# project_buran_schematic.net
KiCad netlist of a schematic drawn in Altium Designer
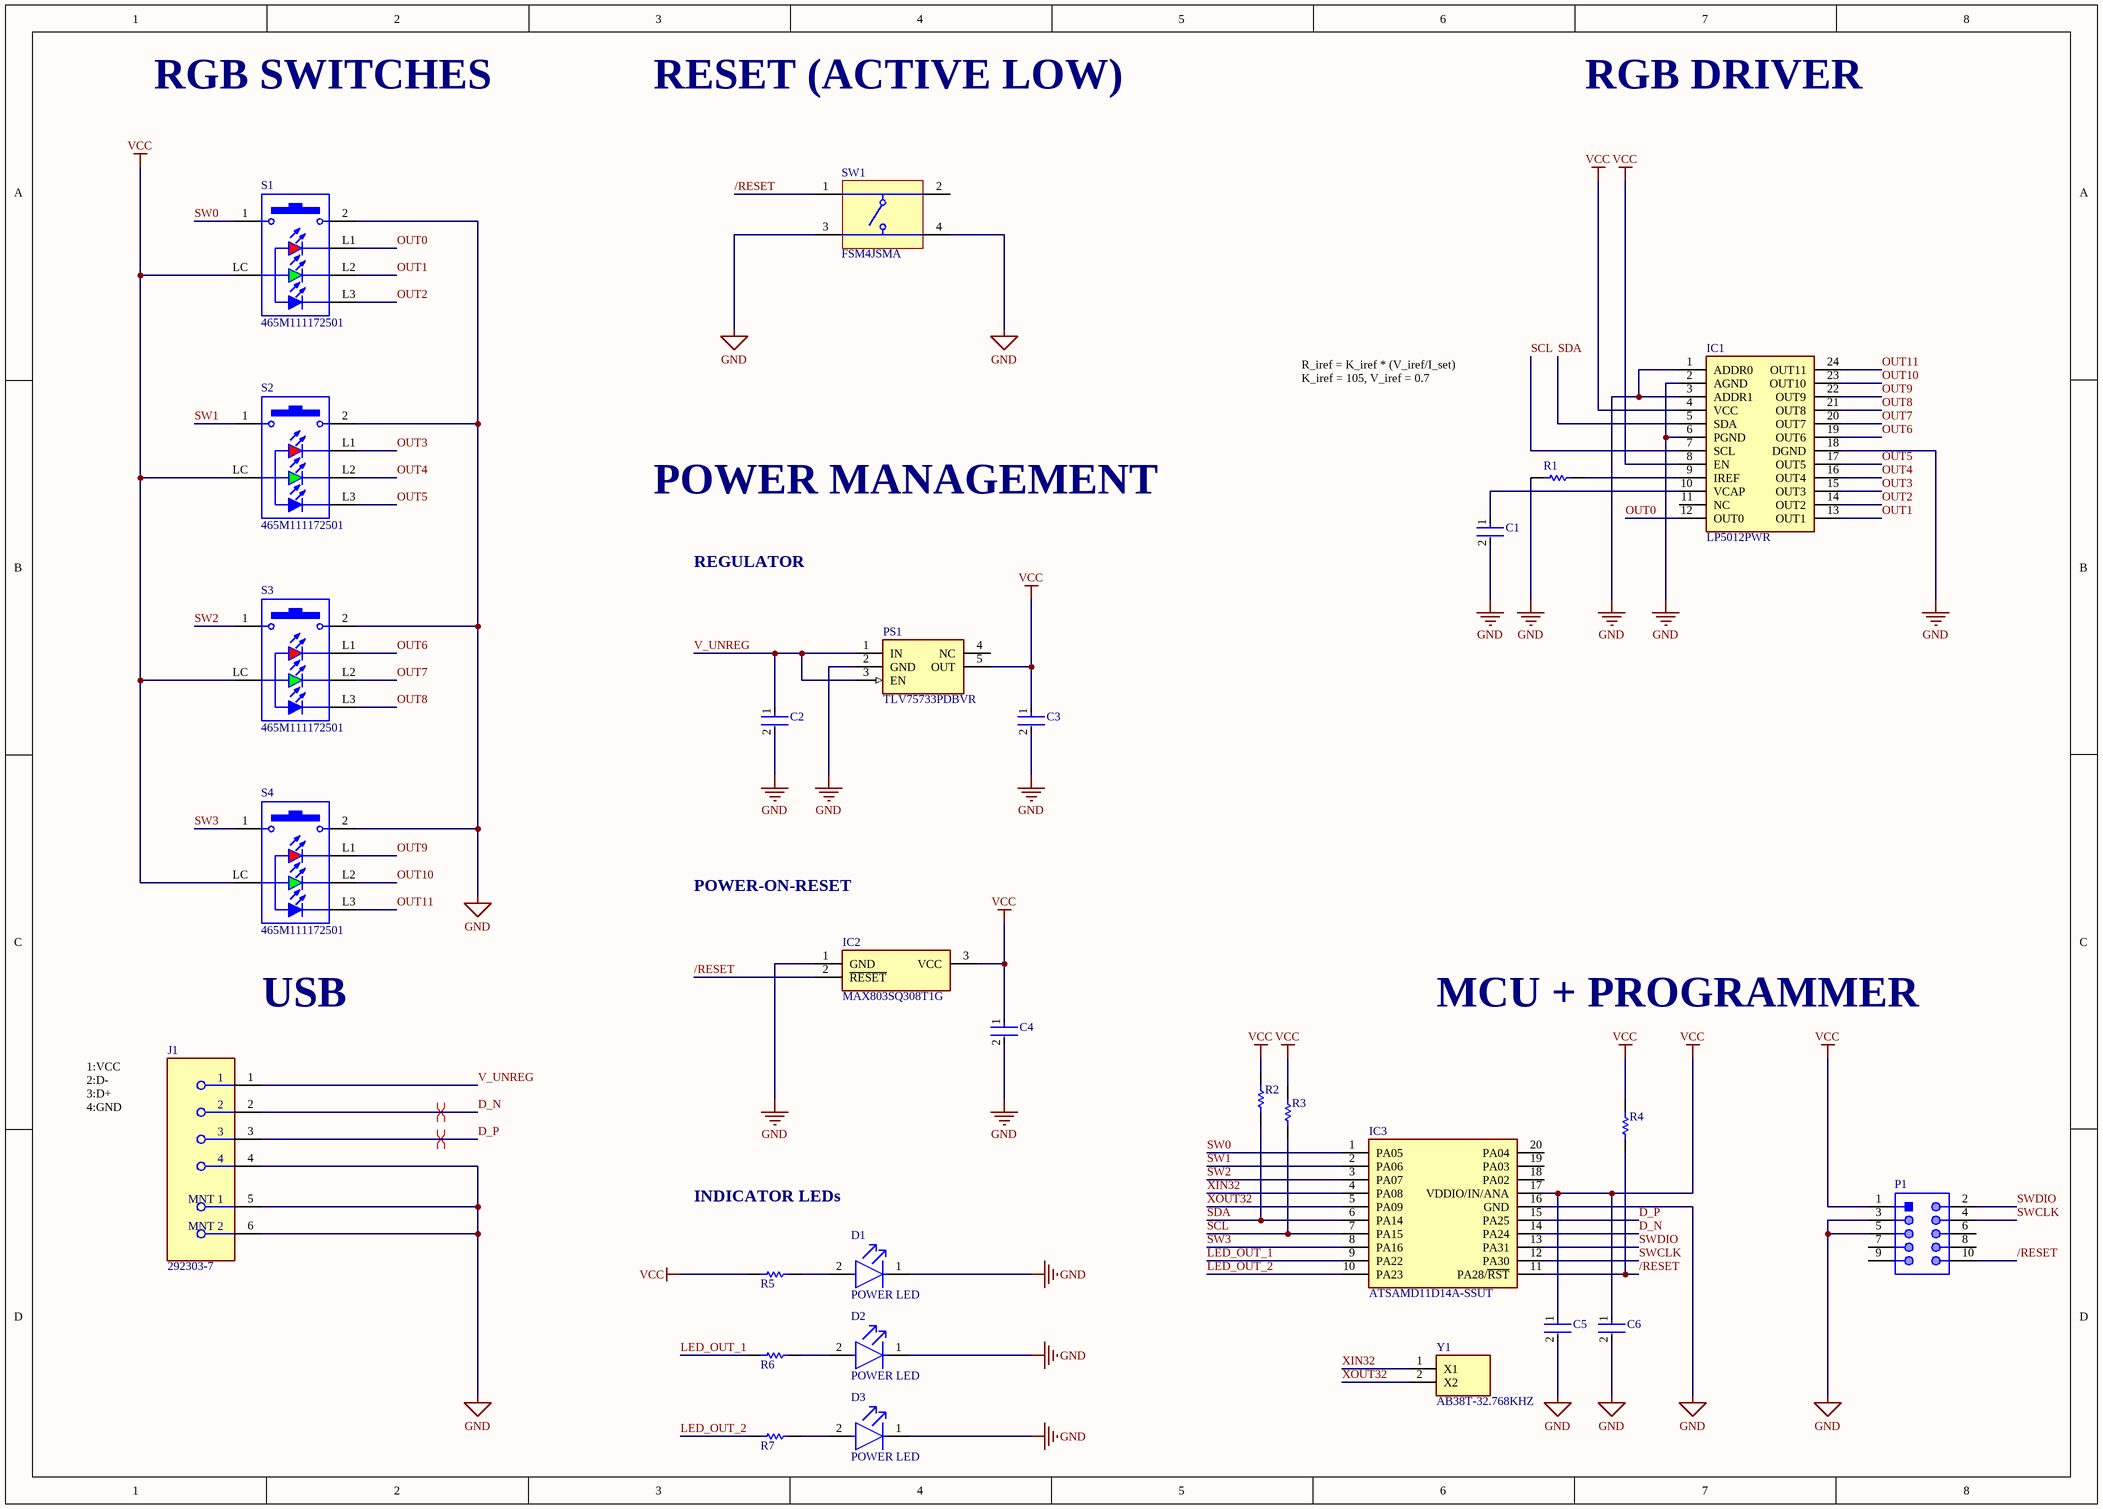
[diagram p0: project_buran_schematic.SchDoc]

(export (version "E")
  (design (tool "Eeschema 10.0.6"))
  (components
    (comp (ref "C1")
      (value "GRM188R60J106ME47D")
      (footprint "FP-GRM188-0_1-e0_2_0_55-IPC_A")
      (description "Chip Multilayer Ceramic Capacitors for General Purpose, 0603, 10uF, X5R, 15%, 20%, 6.3V")
      (fields (field (name "VOLTAGE") "6.3V") (field (name "TOLERANCE") "20%"))
      (libsource (lib "Altium Content Vault") (part "02cd4be3c70576c341d710602a673aa"))
    )
    (comp (ref "C2")
      (value "GRM188R60J106ME47D")
      (footprint "FP-GRM188-0_1-e0_2_0_55-IPC_A")
      (description "Chip Multilayer Ceramic Capacitors for General Purpose, 0603, 10uF, X5R, 15%, 20%, 6.3V")
      (fields (field (name "VOLTAGE") "6.3V") (field (name "TOLERANCE") "20%"))
      (libsource (lib "Altium Content Vault") (part "02cd4be3c70576c341d710602a673aa"))
    )
    (comp (ref "C3")
      (value "GRM188R60J106ME47D")
      (footprint "FP-GRM188-0_1-e0_2_0_55-IPC_A")
      (description "Chip Multilayer Ceramic Capacitors for General Purpose, 0603, 10uF, X5R, 15%, 20%, 6.3V")
      (fields (field (name "VOLTAGE") "6.3V") (field (name "TOLERANCE") "20%"))
      (libsource (lib "Altium Content Vault") (part "02cd4be3c70576c341d710602a673aa"))
    )
    (comp (ref "C4")
      (value "GRM188R60J106ME47D")
      (footprint "FP-GRM188-0_1-e0_2_0_55-IPC_A")
      (description "Chip Multilayer Ceramic Capacitors for General Purpose, 0603, 10uF, X5R, 15%, 20%, 6.3V")
      (fields (field (name "VOLTAGE") "6.3V") (field (name "TOLERANCE") "20%"))
      (libsource (lib "Altium Content Vault") (part "02cd4be3c70576c341d710602a673aa"))
    )
    (comp (ref "C5")
      (value "GRM188R60J106ME47D")
      (footprint "FP-GRM188-0_1-e0_2_0_55-IPC_A")
      (description "Chip Multilayer Ceramic Capacitors for General Purpose, 0603, 10uF, X5R, 15%, 20%, 6.3V")
      (fields (field (name "VOLTAGE") "6.3V") (field (name "TOLERANCE") "20%"))
      (libsource (lib "Altium Content Vault") (part "02cd4be3c70576c341d710602a673aa"))
    )
    (comp (ref "C6")
      (value "GRM188R60J106ME47D")
      (footprint "FP-GRM188-0_1-e0_2_0_55-IPC_A")
      (description "Chip Multilayer Ceramic Capacitors for General Purpose, 0603, 10uF, X5R, 15%, 20%, 6.3V")
      (fields (field (name "VOLTAGE") "6.3V") (field (name "TOLERANCE") "20%"))
      (libsource (lib "Altium Content Vault") (part "02cd4be3c70576c341d710602a673aa"))
    )
    (comp (ref "D1")
      (value "POWER LED")
      (footprint "FP-LTST-C190GKT-MFG")
      (description "LED GREEN CLEAR CHIP SMD")
      (fields (field (name "VOLTAGE") "2V"))
      (libsource (lib "Altium Content Vault") (part "8706943c75ba83719d021d2fdc84c58"))
    )
    (comp (ref "D2")
      (value "POWER LED")
      (footprint "FP-LTST-C190GKT-MFG")
      (description "LED GREEN CLEAR CHIP SMD")
      (fields (field (name "VOLTAGE") "2V"))
      (libsource (lib "Altium Content Vault") (part "8706943c75ba83719d021d2fdc84c58"))
    )
    (comp (ref "D3")
      (value "POWER LED")
      (footprint "FP-LTST-C190GKT-MFG")
      (description "LED GREEN CLEAR CHIP SMD")
      (fields (field (name "VOLTAGE") "2V"))
      (libsource (lib "Altium Content Vault") (part "8706943c75ba83719d021d2fdc84c58"))
    )
    (comp (ref "IC1")
      (value "LP5012PWR")
      (footprint "SOP65P640X120-24N")
      (description "Integrated Circuit")
      (fields (field (name "MOUSER PART NUMBER") "595-LP5012PWR"))
      (libsource (lib "*") (part "LP5012PWR"))
    )
    (comp (ref "IC2")
      (value "MAX803SQ308T1G")
      (footprint "SamacSys:SOT65P220X100-3N")
      (description "Integrated Circuit")
      (fields (field (name "MOUSER PART NUMBER") "863-MAX803SQ308T1G"))
      (libsource (lib "*") (part "MAX803SQ308T1G"))
    )
    (comp (ref "IC3")
      (value "ATSAMD11D14A-SSUT")
      (footprint "SamacSys:SOIC127P1032X265-20N")
      (description "Integrated Circuit")
      (fields (field (name "MOUSER PART NUMBER") "556-ATSAMD11D14ASSUT"))
      (libsource (lib "*") (part "ATSAMD11D14A-SSUT"))
    )
    (comp (ref "J1")
      (value "292303-7")
      (footprint "FP-292303-7-MFG")
      (description "CONN RCPT USB2.0 TYPEA 4P SMD RA")
      (fields
        (field (name "OCTOPART") "https://octopart.com/292303-7-te+connectivity-42840369")
        (field (name "MANUFACTURER") "TE Connectivity")
      )
      (libsource (lib "Altium Content Vault") (part "79e6714efa0bb2f851c24b2688127c9"))
    )
    (comp (ref "P1")
      (value "61301021121")
      (footprint "61301021121")
      (description "THT Vertical Pin Header WR-PHD, Pitch 2.54 mm, Dual Row, 10 pins")
      (fields (field (name "MANUFACTURER") "Wurth Elektronik") (field (name "PUBLISHER") "WurthElektronik"))
      (libsource (lib "Altium Content Vault") (part "WE-CN-2P-M-R10"))
    )
    (comp (ref "PS1")
      (value "TLV75733PDBVR")
      (footprint "SamacSys:SOT95P280X145-5N")
      (description "Power Supply")
      (fields (field (name "MOUSER PART NUMBER") "595-TLV75733PDBVR"))
      (libsource (lib "SamacSys") (part "TLV75733PDBVR"))
    )
    (comp (ref "R1")
      (value "CRCW0603110RFKEA")
      (footprint "RESC1609X50X30NL10T20")
      (fields (field (name "MANUFACTURER") "Vishay Dale"))
      (libsource (lib "Altium Content Vault") (part "RES"))
    )
    (comp (ref "R2")
      (value "CRCW0603110RFKEA")
      (footprint "RESC1609X50X30NL10T20")
      (fields (field (name "MANUFACTURER") "Vishay Dale"))
      (libsource (lib "Altium Content Vault") (part "RES"))
    )
    (comp (ref "R3")
      (value "CRCW0603110RFKEA")
      (footprint "RESC1609X50X30NL10T20")
      (fields (field (name "MANUFACTURER") "Vishay Dale"))
      (libsource (lib "Altium Content Vault") (part "RES"))
    )
    (comp (ref "R4")
      (value "CRCW0603110RFKEA")
      (footprint "RESC1609X50X30NL10T20")
      (fields (field (name "MANUFACTURER") "Vishay Dale"))
      (libsource (lib "Altium Content Vault") (part "RES"))
    )
    (comp (ref "R5")
      (value "CRCW0603110RFKEA")
      (footprint "RESC1609X50X30NL10T20")
      (fields (field (name "MANUFACTURER") "Vishay Dale"))
      (libsource (lib "Altium Content Vault") (part "RES"))
    )
    (comp (ref "R6")
      (value "CRCW0603110RFKEA")
      (footprint "RESC1609X50X30NL10T20")
      (fields (field (name "MANUFACTURER") "Vishay Dale"))
      (libsource (lib "Altium Content Vault") (part "RES"))
    )
    (comp (ref "R7")
      (value "CRCW0603110RFKEA")
      (footprint "RESC1609X50X30NL10T20")
      (fields (field (name "MANUFACTURER") "Vishay Dale"))
      (libsource (lib "Altium Content Vault") (part "RES"))
    )
    (comp (ref "S1")
      (value "465M111172501")
      (footprint "465M111172501")
      (description "WS-PBTL Illuminated THT Push Button Switch, Red & Green & Blue")
      (fields (field (name "PUBLISHER") "Wurth Elektronik"))
      (libsource (lib "Altium_WS-PBTL (rev19a)") (part "465M111172501"))
    )
    (comp (ref "S2")
      (value "465M111172501")
      (footprint "465M111172501")
      (description "WS-PBTL Illuminated THT Push Button Switch, Red & Green & Blue")
      (fields (field (name "PUBLISHER") "Wurth Elektronik"))
      (libsource (lib "Altium_WS-PBTL (rev19a)") (part "465M111172501"))
    )
    (comp (ref "S3")
      (value "465M111172501")
      (footprint "465M111172501")
      (description "WS-PBTL Illuminated THT Push Button Switch, Red & Green & Blue")
      (fields (field (name "PUBLISHER") "Wurth Elektronik"))
      (libsource (lib "Altium_WS-PBTL (rev19a)") (part "465M111172501"))
    )
    (comp (ref "S4")
      (value "465M111172501")
      (footprint "465M111172501")
      (description "WS-PBTL Illuminated THT Push Button Switch, Red & Green & Blue")
      (fields (field (name "PUBLISHER") "Wurth Elektronik"))
      (libsource (lib "Altium_WS-PBTL (rev19a)") (part "465M111172501"))
    )
    (comp (ref "SW1")
      (value "FSM4JSMA")
      (footprint "TECO-FSM4JSMA_V")
      (description "Swicth, SPST, 24 V, -35 to 85 degC, 4-Pin SMD, RoHS, Tape and Reel")
      (fields (field (name "MANUFACTURER") "TE Connectivity"))
      (libsource (lib "Altium Content Vault") (part "SW-SPST-4_A"))
    )
    (comp (ref "Y1")
      (value "AB38T-32.768KHZ")
      (footprint "SamacSys:AB38T32768KHZ")
      (description "Crystal or Oscillator")
      (fields (field (name "MOUSER PART NUMBER") "815-AB38T-32.768KHZ"))
      (libsource (lib "SamacSys") (part "AB38T-32.768KHZ"))
    )
  )
  (nets
    (net (code "1") (name "/D_N") (class "Default")
      (node (ref "IC3") (pin "14") (pinfunction "PA24_14") (pintype "passive"))
      (node (ref "J1") (pin "2") (pinfunction "2_2") (pintype "passive"))
    )
    (net (code "2") (name "/D_P") (class "Default")
      (node (ref "IC3") (pin "15") (pinfunction "PA25_15") (pintype "passive"))
      (node (ref "J1") (pin "3") (pinfunction "3_3") (pintype "passive"))
    )
    (net (code "3") (name "/LED_OUT_1") (class "Default")
      (node (ref "IC3") (pin "9") (pinfunction "PA22_9") (pintype "passive"))
      (node (ref "R6") (pin "2") (pinfunction "2_2") (pintype "passive"))
    )
    (net (code "4") (name "/LED_OUT_2") (class "Default")
      (node (ref "IC3") (pin "10") (pinfunction "PA23_10") (pintype "passive"))
      (node (ref "R7") (pin "2") (pinfunction "2_2") (pintype "passive"))
    )
    (net (code "5") (name "/OUT0") (class "Default")
      (node (ref "IC1") (pin "12") (pinfunction "OUT0_12") (pintype "passive"))
      (node (ref "S1") (pin "L1") (pinfunction "L1_L1") (pintype "passive"))
    )
    (net (code "6") (name "/OUT1") (class "Default")
      (node (ref "IC1") (pin "13") (pinfunction "OUT1_13") (pintype "passive"))
      (node (ref "S1") (pin "L2") (pinfunction "L2_L2") (pintype "passive"))
    )
    (net (code "7") (name "/OUT2") (class "Default")
      (node (ref "IC1") (pin "14") (pinfunction "OUT2_14") (pintype "passive"))
      (node (ref "S1") (pin "L3") (pinfunction "L3_L3") (pintype "passive"))
    )
    (net (code "8") (name "/OUT3") (class "Default")
      (node (ref "IC1") (pin "15") (pinfunction "OUT3_15") (pintype "passive"))
      (node (ref "S2") (pin "L1") (pinfunction "L1_L1") (pintype "passive"))
    )
    (net (code "9") (name "/OUT4") (class "Default")
      (node (ref "IC1") (pin "16") (pinfunction "OUT4_16") (pintype "passive"))
      (node (ref "S2") (pin "L2") (pinfunction "L2_L2") (pintype "passive"))
    )
    (net (code "10") (name "/OUT5") (class "Default")
      (node (ref "IC1") (pin "17") (pinfunction "OUT5_17") (pintype "passive"))
      (node (ref "S2") (pin "L3") (pinfunction "L3_L3") (pintype "passive"))
    )
    (net (code "11") (name "/OUT6") (class "Default")
      (node (ref "IC1") (pin "19") (pinfunction "OUT6_19") (pintype "passive"))
      (node (ref "S3") (pin "L1") (pinfunction "L1_L1") (pintype "passive"))
    )
    (net (code "12") (name "/OUT7") (class "Default")
      (node (ref "IC1") (pin "20") (pinfunction "OUT7_20") (pintype "passive"))
      (node (ref "S3") (pin "L2") (pinfunction "L2_L2") (pintype "passive"))
    )
    (net (code "13") (name "/OUT8") (class "Default")
      (node (ref "IC1") (pin "21") (pinfunction "OUT8_21") (pintype "passive"))
      (node (ref "S3") (pin "L3") (pinfunction "L3_L3") (pintype "passive"))
    )
    (net (code "14") (name "/OUT9") (class "Default")
      (node (ref "IC1") (pin "22") (pinfunction "OUT9_22") (pintype "passive"))
      (node (ref "S4") (pin "L1") (pinfunction "L1_L1") (pintype "passive"))
    )
    (net (code "15") (name "/OUT10") (class "Default")
      (node (ref "IC1") (pin "23") (pinfunction "OUT10_23") (pintype "passive"))
      (node (ref "S4") (pin "L2") (pinfunction "L2_L2") (pintype "passive"))
    )
    (net (code "16") (name "/OUT11") (class "Default")
      (node (ref "IC1") (pin "24") (pinfunction "OUT11_24") (pintype "passive"))
      (node (ref "S4") (pin "L3") (pinfunction "L3_L3") (pintype "passive"))
    )
    (net (code "17") (name "/SCL") (class "Default")
      (node (ref "IC1") (pin "7") (pinfunction "SCL_7") (pintype "passive"))
      (node (ref "IC3") (pin "7") (pinfunction "PA15_7") (pintype "passive"))
      (node (ref "R3") (pin "1") (pinfunction "1_1") (pintype "passive"))
    )
    (net (code "18") (name "/SDA") (class "Default")
      (node (ref "IC1") (pin "5") (pinfunction "SDA_5") (pintype "passive"))
      (node (ref "IC3") (pin "6") (pinfunction "PA14_6") (pintype "passive"))
      (node (ref "R2") (pin "1") (pinfunction "1_1") (pintype "passive"))
    )
    (net (code "19") (name "/SW0") (class "Default")
      (node (ref "IC3") (pin "1") (pinfunction "PA05_1") (pintype "passive"))
      (node (ref "S1") (pin "1") (pinfunction "1_1") (pintype "passive"))
    )
    (net (code "20") (name "/SW1") (class "Default")
      (node (ref "IC3") (pin "2") (pinfunction "PA06_2") (pintype "passive"))
      (node (ref "S2") (pin "1") (pinfunction "1_1") (pintype "passive"))
    )
    (net (code "21") (name "/SW2") (class "Default")
      (node (ref "IC3") (pin "3") (pinfunction "PA07_3") (pintype "passive"))
      (node (ref "S3") (pin "1") (pinfunction "1_1") (pintype "passive"))
    )
    (net (code "22") (name "/SW3") (class "Default")
      (node (ref "IC3") (pin "8") (pinfunction "PA16_8") (pintype "passive"))
      (node (ref "S4") (pin "1") (pinfunction "1_1") (pintype "passive"))
    )
    (net (code "23") (name "/SWCLK") (class "Default")
      (node (ref "IC3") (pin "12") (pinfunction "PA30_12") (pintype "passive"))
      (node (ref "P1") (pin "4") (pinfunction "4_4") (pintype "passive"))
    )
    (net (code "24") (name "/SWDIO") (class "Default")
      (node (ref "IC3") (pin "13") (pinfunction "PA31_13") (pintype "passive"))
      (node (ref "P1") (pin "2") (pinfunction "2_2") (pintype "passive"))
    )
    (net (code "25") (name "/V_UNREG") (class "Default")
      (node (ref "C2") (pin "1") (pinfunction "1_1") (pintype "passive"))
      (node (ref "J1") (pin "1") (pinfunction "1_1") (pintype "passive"))
      (node (ref "PS1") (pin "1") (pinfunction "IN_1") (pintype "power_in"))
      (node (ref "PS1") (pin "3") (pinfunction "EN_3") (pintype "input"))
    )
    (net (code "26") (name "/XIN32") (class "Default")
      (node (ref "IC3") (pin "4") (pinfunction "PA08_4") (pintype "passive"))
      (node (ref "Y1") (pin "1") (pinfunction "X1_1") (pintype "passive"))
    )
    (net (code "27") (name "/XOUT32") (class "Default")
      (node (ref "IC3") (pin "5") (pinfunction "PA09_5") (pintype "passive"))
      (node (ref "Y1") (pin "2") (pinfunction "X2_2") (pintype "passive"))
    )
    (net (code "28") (name "/{slash}RESET") (class "Default")
      (node (ref "IC2") (pin "2") (pinfunction "~{RESET}_2") (pintype "passive"))
      (node (ref "IC3") (pin "11") (pinfunction "PA28/~{RST}_11") (pintype "passive"))
      (node (ref "P1") (pin "10") (pinfunction "10_10") (pintype "passive"))
      (node (ref "R4") (pin "1") (pinfunction "1_1") (pintype "passive"))
      (node (ref "SW1") (pin "1") (pinfunction "1_1") (pintype "passive"))
    )
    (net (code "29") (name "GND") (class "Default")
      (node (ref "C1") (pin "2") (pinfunction "2_2") (pintype "passive"))
      (node (ref "C2") (pin "2") (pinfunction "2_2") (pintype "passive"))
      (node (ref "C3") (pin "2") (pinfunction "2_2") (pintype "passive"))
      (node (ref "C4") (pin "2") (pinfunction "2_2") (pintype "passive"))
      (node (ref "C5") (pin "2") (pinfunction "2_2") (pintype "passive"))
      (node (ref "C6") (pin "2") (pinfunction "2_2") (pintype "passive"))
      (node (ref "D1") (pin "1") (pinfunction "C_1") (pintype "passive"))
      (node (ref "D2") (pin "1") (pinfunction "C_1") (pintype "passive"))
      (node (ref "D3") (pin "1") (pinfunction "C_1") (pintype "passive"))
      (node (ref "IC1") (pin "1") (pinfunction "ADDR0_1") (pintype "passive"))
      (node (ref "IC1") (pin "18") (pinfunction "DGND_18") (pintype "passive"))
      (node (ref "IC1") (pin "2") (pinfunction "AGND_2") (pintype "passive"))
      (node (ref "IC1") (pin "3") (pinfunction "ADDR1_3") (pintype "passive"))
      (node (ref "IC1") (pin "6") (pinfunction "PGND_6") (pintype "passive"))
      (node (ref "IC2") (pin "1") (pinfunction "GND_1") (pintype "power_in"))
      (node (ref "IC3") (pin "16") (pinfunction "GND_16") (pintype "passive"))
      (node (ref "J1") (pin "4") (pinfunction "4_4") (pintype "passive"))
      (node (ref "J1") (pin "5") (pinfunction "MNT_1_5") (pintype "passive"))
      (node (ref "J1") (pin "6") (pinfunction "MNT_2_6") (pintype "passive"))
      (node (ref "P1") (pin "3") (pinfunction "3_3") (pintype "passive"))
      (node (ref "P1") (pin "5") (pinfunction "5_5") (pintype "passive"))
      (node (ref "PS1") (pin "2") (pinfunction "GND_2") (pintype "power_in"))
      (node (ref "R1") (pin "1") (pinfunction "1_1") (pintype "passive"))
      (node (ref "S1") (pin "2") (pinfunction "2_2") (pintype "passive"))
      (node (ref "S2") (pin "2") (pinfunction "2_2") (pintype "passive"))
      (node (ref "S3") (pin "2") (pinfunction "2_2") (pintype "passive"))
      (node (ref "S4") (pin "2") (pinfunction "2_2") (pintype "passive"))
      (node (ref "SW1") (pin "3") (pinfunction "3_3") (pintype "passive"))
      (node (ref "SW1") (pin "4") (pinfunction "4_4") (pintype "passive"))
    )
    (net (code "30") (name "Net-(D1-A)") (class "Default")
      (node (ref "D1") (pin "2") (pinfunction "A_2") (pintype "passive"))
      (node (ref "R5") (pin "1") (pinfunction "1_1") (pintype "passive"))
    )
    (net (code "31") (name "Net-(D2-A)") (class "Default")
      (node (ref "D2") (pin "2") (pinfunction "A_2") (pintype "passive"))
      (node (ref "R6") (pin "1") (pinfunction "1_1") (pintype "passive"))
    )
    (net (code "32") (name "Net-(D3-A)") (class "Default")
      (node (ref "D3") (pin "2") (pinfunction "A_2") (pintype "passive"))
      (node (ref "R7") (pin "1") (pinfunction "1_1") (pintype "passive"))
    )
    (net (code "33") (name "Net-(IC1-IREF)") (class "Default")
      (node (ref "IC1") (pin "9") (pinfunction "IREF_9") (pintype "passive"))
      (node (ref "R1") (pin "2") (pinfunction "2_2") (pintype "passive"))
    )
    (net (code "34") (name "Net-(IC1-VCAP)") (class "Default")
      (node (ref "C1") (pin "1") (pinfunction "1_1") (pintype "passive"))
      (node (ref "IC1") (pin "10") (pinfunction "VCAP_10") (pintype "passive"))
    )
    (net (code "35") (name "VCC") (class "Default")
      (node (ref "C3") (pin "1") (pinfunction "1_1") (pintype "passive"))
      (node (ref "C4") (pin "1") (pinfunction "1_1") (pintype "passive"))
      (node (ref "C5") (pin "1") (pinfunction "1_1") (pintype "passive"))
      (node (ref "C6") (pin "1") (pinfunction "1_1") (pintype "passive"))
      (node (ref "IC1") (pin "4") (pinfunction "VCC_4") (pintype "passive"))
      (node (ref "IC1") (pin "8") (pinfunction "EN_8") (pintype "passive"))
      (node (ref "IC2") (pin "3") (pinfunction "VCC_3") (pintype "power_in"))
      (node (ref "IC3") (pin "17") (pinfunction "VDDIO/IN/ANA_17") (pintype "passive"))
      (node (ref "P1") (pin "1") (pinfunction "1_1") (pintype "passive"))
      (node (ref "PS1") (pin "5") (pinfunction "OUT_5") (pintype "power_in"))
      (node (ref "R2") (pin "2") (pinfunction "2_2") (pintype "passive"))
      (node (ref "R3") (pin "2") (pinfunction "2_2") (pintype "passive"))
      (node (ref "R4") (pin "2") (pinfunction "2_2") (pintype "passive"))
      (node (ref "R5") (pin "2") (pinfunction "2_2") (pintype "passive"))
      (node (ref "S1") (pin "LC") (pinfunction "LC_LC") (pintype "passive"))
      (node (ref "S2") (pin "LC") (pinfunction "LC_LC") (pintype "passive"))
      (node (ref "S3") (pin "LC") (pinfunction "LC_LC") (pintype "passive"))
      (node (ref "S4") (pin "LC") (pinfunction "LC_LC") (pintype "passive"))
    )
    (net (code "36") (name "unconnected-(IC1-NC-Pad11)") (class "Default")
      (node (ref "IC1") (pin "11") (pinfunction "NC_11") (pintype "passive"))
    )
    (net (code "37") (name "unconnected-(IC3-PA02-Pad18)") (class "Default")
      (node (ref "IC3") (pin "18") (pinfunction "PA02_18") (pintype "passive"))
    )
    (net (code "38") (name "unconnected-(IC3-PA03-Pad19)") (class "Default")
      (node (ref "IC3") (pin "19") (pinfunction "PA03_19") (pintype "passive"))
    )
    (net (code "39") (name "unconnected-(IC3-PA04-Pad20)") (class "Default")
      (node (ref "IC3") (pin "20") (pinfunction "PA04_20") (pintype "passive"))
    )
    (net (code "40") (name "unconnected-(P1-Pad6)") (class "Default")
      (node (ref "P1") (pin "6") (pinfunction "6_6") (pintype "passive"))
    )
    (net (code "41") (name "unconnected-(P1-Pad7)") (class "Default")
      (node (ref "P1") (pin "7") (pinfunction "7_7") (pintype "passive"))
    )
    (net (code "42") (name "unconnected-(P1-Pad8)") (class "Default")
      (node (ref "P1") (pin "8") (pinfunction "8_8") (pintype "passive"))
    )
    (net (code "43") (name "unconnected-(P1-Pad9)") (class "Default")
      (node (ref "P1") (pin "9") (pinfunction "9_9") (pintype "passive"))
    )
    (net (code "44") (name "unconnected-(PS1-NC-Pad4)") (class "Default")
      (node (ref "PS1") (pin "4") (pinfunction "NC_4") (pintype "passive"))
    )
    (net (code "45") (name "unconnected-(SW1-Pad2)") (class "Default")
      (node (ref "SW1") (pin "2") (pinfunction "2_2") (pintype "passive"))
    )
  )
)
